# CW308T_ATMegaRF_Micro.net
KiCad netlist of a schematic drawn in Altium Designer
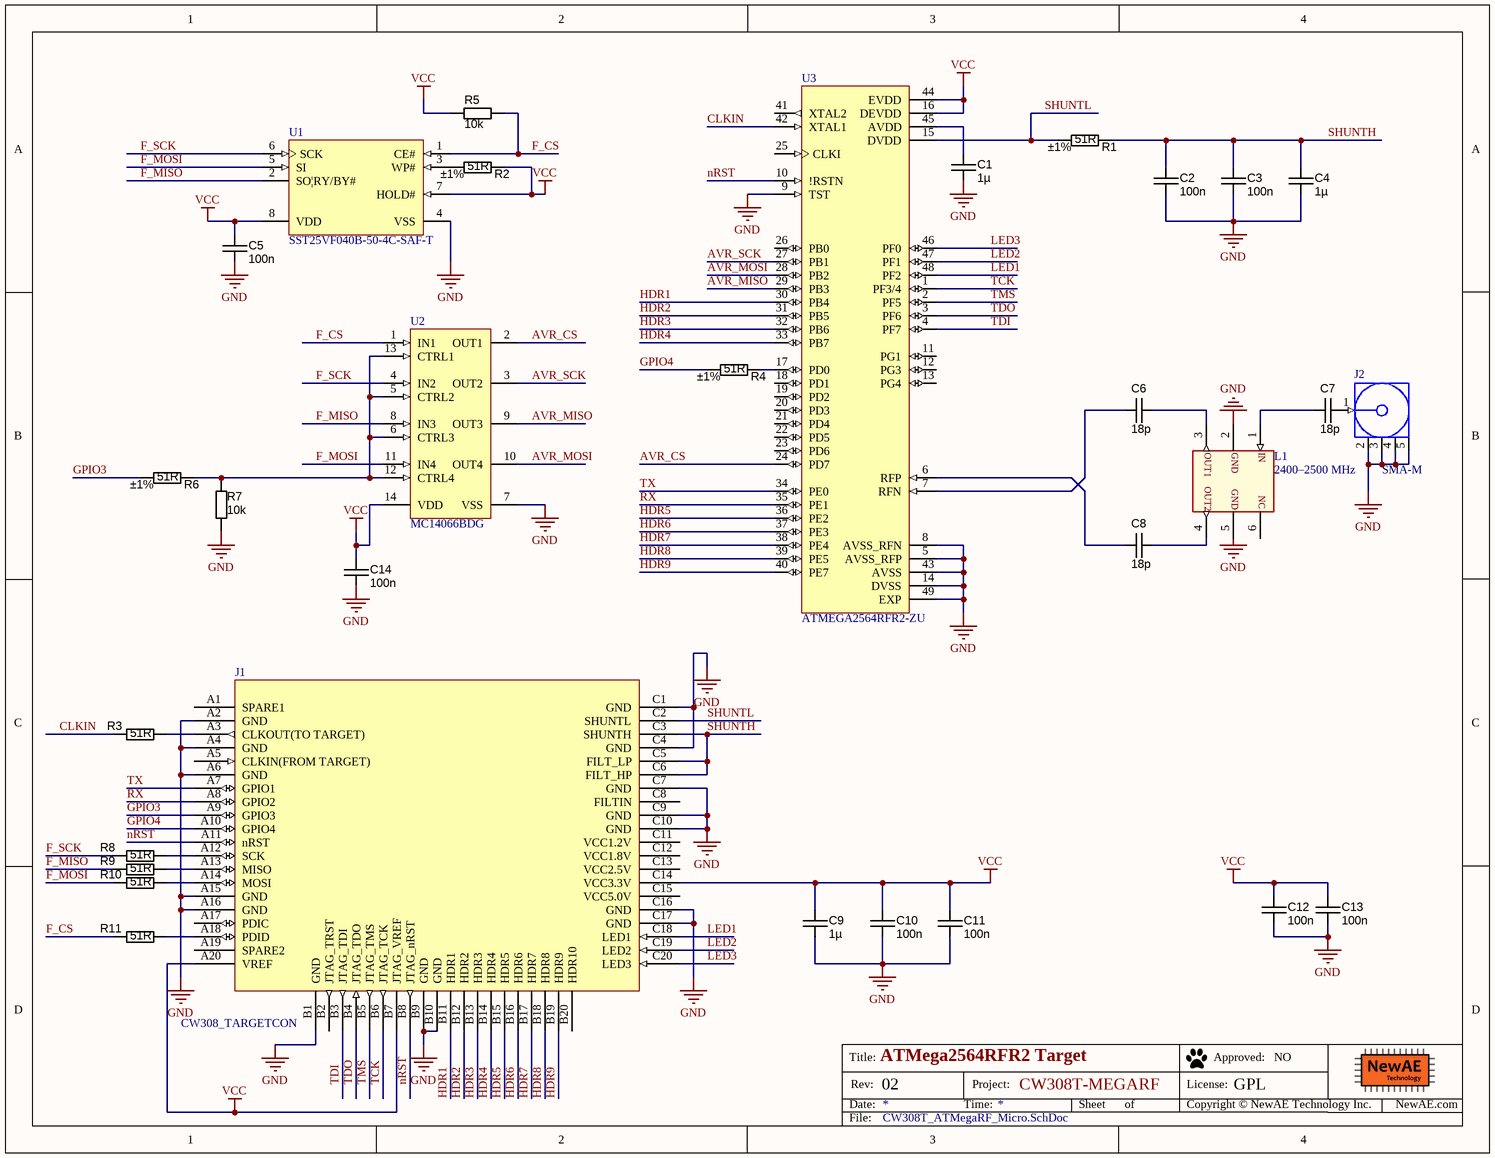
[diagram p0: CW308T_ATMegaRF_Micro.SchDoc]

(export (version "E")
  (design (tool "Eeschema 10.0.6"))
  (components
    (comp (ref "C1")
      (value "1µ")
      (footprint "CAPC1608X90N")
      (description "Capacitor SMD Cer 1uF 10% 16V X7R 0603")
      (fields (field (name "TOLERANCE") "±10%") (field (name "Comment") "approved sub OK"))
      (libsource (lib "PBL - Capacitors") (part "CAPC_1u_0603_X7R_16V_10%"))
    )
    (comp (ref "C2")
      (value "100n")
      (footprint "CAPC1608X90N")
      (description "Capacitor SMD Cer 100nF 10% 50V X7R 0603")
      (fields (field (name "TOLERANCE") "±10%") (field (name "Comment") "approved sub OK"))
      (libsource (lib "PBL - Capacitors") (part "CAPC_100n_0603_X7R_50V_10%"))
    )
    (comp (ref "C3")
      (value "100n")
      (footprint "CAPC1608X90N")
      (description "Capacitor SMD Cer 100nF 10% 50V X7R 0603")
      (fields (field (name "TOLERANCE") "±10%") (field (name "Comment") "approved sub OK"))
      (libsource (lib "PBL - Capacitors") (part "CAPC_100n_0603_X7R_50V_10%"))
    )
    (comp (ref "C4")
      (value "1µ")
      (footprint "CAPC1608X90N")
      (description "Capacitor SMD Cer 1uF 10% 16V X7R 0603")
      (fields (field (name "TOLERANCE") "±10%") (field (name "Comment") "approved sub OK"))
      (libsource (lib "PBL - Capacitors") (part "CAPC_1u_0603_X7R_16V_10%"))
    )
    (comp (ref "C5")
      (value "100n")
      (footprint "CAPC1608X90N")
      (description "Capacitor SMD Cer 100nF 10% 50V X7R 0603")
      (fields (field (name "TOLERANCE") "±10%") (field (name "Comment") "approved sub OK"))
      (libsource (lib "PBL - Capacitors") (part "CAPC_100n_0603_X7R_50V_10%"))
    )
    (comp (ref "C6")
      (value "18p")
      (footprint "CAPC1608X90N")
      (description "Capacitor SMD Cer 18pF 2% 100V NP0 0603")
      (fields (field (name "TOLERANCE") "±2%"))
      (libsource (lib "PBL - Capacitors") (part "CAPC_18p_0603_100V"))
    )
    (comp (ref "C7")
      (value "18p")
      (footprint "CAPC1608X90N")
      (description "Capacitor SMD Cer 18pF 2% 100V NP0 0603")
      (fields (field (name "TOLERANCE") "±2%"))
      (libsource (lib "PBL - Capacitors") (part "CAPC_18p_0603_100V"))
    )
    (comp (ref "C8")
      (value "18p")
      (footprint "CAPC1608X90N")
      (description "Capacitor SMD Cer 18pF 2% 100V NP0 0603")
      (fields (field (name "TOLERANCE") "±2%"))
      (libsource (lib "PBL - Capacitors") (part "CAPC_18p_0603_100V"))
    )
    (comp (ref "C9")
      (value "1µ")
      (footprint "CAPC1608X90N")
      (description "Capacitor SMD Cer 1uF 10% 16V X7R 0603")
      (fields (field (name "TOLERANCE") "±10%") (field (name "Comment") "approved sub OK"))
      (libsource (lib "PBL - Capacitors") (part "CAPC_1u_0603_X7R_16V_10%"))
    )
    (comp (ref "C10")
      (value "100n")
      (footprint "CAPC1608X90N")
      (description "Capacitor SMD Cer 100nF 10% 50V X7R 0603")
      (fields (field (name "TOLERANCE") "±10%") (field (name "Comment") "approved sub OK"))
      (libsource (lib "PBL - Capacitors") (part "CAPC_100n_0603_X7R_50V_10%"))
    )
    (comp (ref "C11")
      (value "100n")
      (footprint "CAPC1608X90N")
      (description "Capacitor SMD Cer 100nF 10% 50V X7R 0603")
      (fields (field (name "TOLERANCE") "±10%") (field (name "Comment") "approved sub OK"))
      (libsource (lib "PBL - Capacitors") (part "CAPC_100n_0603_X7R_50V_10%"))
    )
    (comp (ref "C12")
      (value "100n")
      (footprint "CAPC1608X90N")
      (description "Capacitor SMD Cer 100nF 10% 50V X7R 0603")
      (fields (field (name "TOLERANCE") "±10%") (field (name "Comment") "approved sub OK"))
      (libsource (lib "PBL - Capacitors") (part "CAPC_100n_0603_X7R_50V_10%"))
    )
    (comp (ref "C13")
      (value "100n")
      (footprint "CAPC1608X90N")
      (description "Capacitor SMD Cer 100nF 10% 50V X7R 0603")
      (fields (field (name "TOLERANCE") "±10%") (field (name "Comment") "approved sub OK"))
      (libsource (lib "PBL - Capacitors") (part "CAPC_100n_0603_X7R_50V_10%"))
    )
    (comp (ref "C14")
      (value "100n")
      (footprint "CAPC1608X90N")
      (description "Capacitor SMD Cer 100nF 10% 50V X7R 0603")
      (fields (field (name "TOLERANCE") "±10%") (field (name "Comment") "approved sub OK"))
      (libsource (lib "PBL - Capacitors") (part "CAPC_100n_0603_X7R_50V_10%"))
    )
    (comp (ref "J1")
      (value "CW308_TARGETCON")
      (footprint "ChipWhisperer_AltiumLib:CW308_TBOARD_CONN")
      (description "CW308 \"Standard\" Target Board Connector")
      (libsource (lib "ChipWhisperer_AltiumLib") (part "CW308_TBOARD"))
    )
    (comp (ref "J2")
      (value "SMA-M")
      (footprint "CON-SMAM-PCB-EDGE062")
      (description "SMA Female Edge Mount Connector for 0.062\" Thick Board")
      (libsource (lib "NewAE_AltiumLib") (part "CON-SMA-PCBEDGE-003.062"))
    )
    (comp (ref "L1")
      (value "2400–2500 MHz")
      (footprint "WE-BAL_0603")
      (description "WE-BAL Multilayer Chip Balun, Frequence=2400–2500 MHz")
      (fields
        (field (name "PARTNO") "748411245")
        (field (name "MANUFACTURER") "Wurth Elektronik")
        (field (name "CREATED BY") "Baojun Chen")
      )
      (libsource (lib "Altium_WE-BAL_rev15a") (part "WE-BAL 0603, 748411245"))
    )
    (comp (ref "R1")
      (value "51R")
      (footprint "RESC1608X55N")
      (description "Resistor SMD chip 51 Ohm 0.1W 1% 0603")
      (fields (field (name "TOLERANCE") "±1%") (field (name "Comment") "Thick Film"))
      (libsource (lib "PBL - Resistors") (part "RES_51R_0603_1%"))
    )
    (comp (ref "R2")
      (value "51R")
      (footprint "RESC1608X55N")
      (description "Resistor SMD chip 51 Ohm 0.1W 1% 0603")
      (fields (field (name "TOLERANCE") "±1%") (field (name "Comment") "Thick Film"))
      (libsource (lib "PBL - Resistors") (part "RES_51R_0603_1%"))
    )
    (comp (ref "R3")
      (value "51R")
      (footprint "RESC1608X55N")
      (description "Resistor SMD chip 51 Ohm 0.1W 1% 0603")
      (fields (field (name "Comment") "Thick Film"))
      (libsource (lib "PBL - Resistors") (part "RES_51R_0603_1%"))
    )
    (comp (ref "R4")
      (value "51R")
      (footprint "RESC1608X55N")
      (description "Resistor SMD chip 51 Ohm 0.1W 1% 0603")
      (fields (field (name "TOLERANCE") "±1%") (field (name "Comment") "Thick Film"))
      (libsource (lib "PBL - Resistors") (part "RES_51R_0603_1%"))
    )
    (comp (ref "R5")
      (value "10k")
      (footprint "RESC1608X55N")
      (description "Resistor SMD chip 3.3k Ohm 0.1W 5% 0603")
      (fields (field (name "TOLERANCE") "±5%") (field (name "Comment") "Thick Film"))
      (libsource (lib "PBL - Resistors") (part "RES_3K3_0603_5%"))
    )
    (comp (ref "R6")
      (value "51R")
      (footprint "RESC1608X55N")
      (description "Resistor SMD chip 51 Ohm 0.1W 1% 0603")
      (fields (field (name "TOLERANCE") "±1%") (field (name "Comment") "Thick Film"))
      (libsource (lib "PBL - Resistors") (part "RES_51R_0603_1%"))
    )
    (comp (ref "R7")
      (value "10k")
      (footprint "RESC1608X55N")
      (description "Resistor SMD chip 3.3k Ohm 0.1W 5% 0603")
      (fields (field (name "TOLERANCE") "±5%") (field (name "Comment") "Thick Film"))
      (libsource (lib "") (part "RES_3K3_0603_5%_1"))
    )
    (comp (ref "R8")
      (value "51R")
      (footprint "RESC1608X55N")
      (description "Resistor SMD chip 51 Ohm 0.1W 1% 0603")
      (fields (field (name "Comment") "Thick Film"))
      (libsource (lib "PBL - Resistors") (part "RES_51R_0603_1%"))
    )
    (comp (ref "R9")
      (value "51R")
      (footprint "RESC1608X55N")
      (description "Resistor SMD chip 51 Ohm 0.1W 1% 0603")
      (fields (field (name "Comment") "Thick Film"))
      (libsource (lib "PBL - Resistors") (part "RES_51R_0603_1%"))
    )
    (comp (ref "R10")
      (value "51R")
      (footprint "RESC1608X55N")
      (description "Resistor SMD chip 51 Ohm 0.1W 1% 0603")
      (fields (field (name "Comment") "Thick Film"))
      (libsource (lib "PBL - Resistors") (part "RES_51R_0603_1%"))
    )
    (comp (ref "R11")
      (value "51R")
      (footprint "RESC1608X55N")
      (description "Resistor SMD chip 51 Ohm 0.1W 1% 0603")
      (fields (field (name "Comment") "Thick Film"))
      (libsource (lib "PBL - Resistors") (part "RES_51R_0603_1%"))
    )
    (comp (ref "U1")
      (value "SST25VF040B-50-4C-SAF-T")
      (footprint "MCHP-SOIC-SA8_N")
      (description "4 Mbit SPI Serial Flash, 2.7 to 3.6 V, 50 MHz, 0 to 70 degC, 8-pin SOIC (SA8), Tape and Reel")
      (fields (field (name "MANUFACTURER") "Microchip"))
      (libsource (lib "Altium Content Vault") (part "CMP-0378-00095-1"))
    )
    (comp (ref "U2")
      (value "MC14066BDG")
      (footprint "ONSC-SOIC-14-751A-03_V")
      (description "Quad Analog Switch / Quad Multiplexer, 3 to 18 V, -55 to 125 degC, 14-Pin SOIC, Pb-Free, Tube")
      (fields (field (name "MANUFACTURER") "On Semiconductor"))
      (libsource (lib "Altium Content Vault") (part "CMP-1307-00073-1"))
    )
    (comp (ref "U3")
      (value "ATMEGA2564RFR2-ZU")
      (footprint "NewAE_AltiumLib:QFN50P700X700X100_HS-49M")
      (description "2.4GHZ 256k SOC 48pin Ind 125C MSL3 - 2.4GHZ 802.15.4 256K SOC 48pin Tray/ VQFN (ZB)")
      (libsource (lib "NewAE_AltiumLib") (part "ATMEGA2565RFR2-ZU"))
    )
  )
  (nets
    (net (code "1") (name "/AVR_CS") (class "Default")
      (node (ref "U2") (pin "2") (pinfunction "OUT1_2") (pintype "tri_state"))
      (node (ref "U3") (pin "24") (pinfunction "PD7_24") (pintype "bidirectional"))
    )
    (net (code "2") (name "/AVR_MISO") (class "Default")
      (node (ref "U2") (pin "9") (pinfunction "OUT3_9") (pintype "tri_state"))
      (node (ref "U3") (pin "29") (pinfunction "PB3_29") (pintype "bidirectional"))
    )
    (net (code "3") (name "/AVR_MOSI") (class "Default")
      (node (ref "U2") (pin "10") (pinfunction "OUT4_10") (pintype "tri_state"))
      (node (ref "U3") (pin "28") (pinfunction "PB2_28") (pintype "bidirectional"))
    )
    (net (code "4") (name "/AVR_SCK") (class "Default")
      (node (ref "U2") (pin "3") (pinfunction "OUT2_3") (pintype "tri_state"))
      (node (ref "U3") (pin "27") (pinfunction "PB1_27") (pintype "bidirectional"))
    )
    (net (code "5") (name "/CLKIN") (class "Default")
      (node (ref "R3") (pin "2") (pinfunction "2_2") (pintype "passive"))
      (node (ref "U3") (pin "42") (pinfunction "XTAL1_42") (pintype "input"))
    )
    (net (code "6") (name "/F_CS") (class "Default")
      (node (ref "R11") (pin "2") (pinfunction "2_2") (pintype "passive"))
      (node (ref "R5") (pin "2") (pinfunction "2_2") (pintype "passive"))
      (node (ref "U1") (pin "1") (pinfunction "CE#_1") (pintype "input"))
      (node (ref "U2") (pin "1") (pinfunction "IN1_1") (pintype "input"))
    )
    (net (code "7") (name "/F_MISO") (class "Default")
      (node (ref "R9") (pin "2") (pinfunction "2_2") (pintype "passive"))
      (node (ref "U1") (pin "2") (pinfunction "SO¦RY/BY#_2") (pintype "tri_state"))
      (node (ref "U2") (pin "8") (pinfunction "IN3_8") (pintype "input"))
    )
    (net (code "8") (name "/F_MOSI") (class "Default")
      (node (ref "R10") (pin "2") (pinfunction "2_2") (pintype "passive"))
      (node (ref "U1") (pin "5") (pinfunction "SI_5") (pintype "input"))
      (node (ref "U2") (pin "11") (pinfunction "IN4_11") (pintype "input"))
    )
    (net (code "9") (name "/F_SCK") (class "Default")
      (node (ref "R8") (pin "2") (pinfunction "2_2") (pintype "passive"))
      (node (ref "U1") (pin "6") (pinfunction "SCK_6") (pintype "input"))
      (node (ref "U2") (pin "4") (pinfunction "IN2_4") (pintype "input"))
    )
    (net (code "10") (name "/GPIO3") (class "Default")
      (node (ref "J1") (pin "A9") (pinfunction "GPIO3_A9") (pintype "bidirectional"))
      (node (ref "R6") (pin "2") (pinfunction "2_2") (pintype "passive"))
    )
    (net (code "11") (name "/GPIO4") (class "Default")
      (node (ref "J1") (pin "A10") (pinfunction "GPIO4_A10") (pintype "bidirectional"))
      (node (ref "R4") (pin "2") (pinfunction "2_2") (pintype "passive"))
    )
    (net (code "12") (name "/HDR1") (class "Default")
      (node (ref "J1") (pin "B11") (pinfunction "HDR1_B11") (pintype "passive"))
      (node (ref "U3") (pin "30") (pinfunction "PB4_30") (pintype "bidirectional"))
    )
    (net (code "13") (name "/HDR2") (class "Default")
      (node (ref "J1") (pin "B12") (pinfunction "HDR2_B12") (pintype "passive"))
      (node (ref "U3") (pin "31") (pinfunction "PB5_31") (pintype "bidirectional"))
    )
    (net (code "14") (name "/HDR3") (class "Default")
      (node (ref "J1") (pin "B13") (pinfunction "HDR3_B13") (pintype "passive"))
      (node (ref "U3") (pin "32") (pinfunction "PB6_32") (pintype "bidirectional"))
    )
    (net (code "15") (name "/HDR4") (class "Default")
      (node (ref "J1") (pin "B14") (pinfunction "HDR4_B14") (pintype "passive"))
      (node (ref "U3") (pin "33") (pinfunction "PB7_33") (pintype "bidirectional"))
    )
    (net (code "16") (name "/HDR5") (class "Default")
      (node (ref "J1") (pin "B15") (pinfunction "HDR5_B15") (pintype "passive"))
      (node (ref "U3") (pin "36") (pinfunction "PE2_36") (pintype "bidirectional"))
    )
    (net (code "17") (name "/HDR6") (class "Default")
      (node (ref "J1") (pin "B16") (pinfunction "HDR6_B16") (pintype "passive"))
      (node (ref "U3") (pin "37") (pinfunction "PE3_37") (pintype "bidirectional"))
    )
    (net (code "18") (name "/HDR7") (class "Default")
      (node (ref "J1") (pin "B17") (pinfunction "HDR7_B17") (pintype "passive"))
      (node (ref "U3") (pin "38") (pinfunction "PE4_38") (pintype "bidirectional"))
    )
    (net (code "19") (name "/HDR8") (class "Default")
      (node (ref "J1") (pin "B18") (pinfunction "HDR8_B18") (pintype "passive"))
      (node (ref "U3") (pin "39") (pinfunction "PE5_39") (pintype "bidirectional"))
    )
    (net (code "20") (name "/HDR9") (class "Default")
      (node (ref "J1") (pin "B19") (pinfunction "HDR9_B19") (pintype "passive"))
      (node (ref "U3") (pin "40") (pinfunction "PE7_40") (pintype "bidirectional"))
    )
    (net (code "21") (name "/LED1") (class "Default")
      (node (ref "J1") (pin "C18") (pinfunction "LED1_C18") (pintype "input"))
      (node (ref "U3") (pin "48") (pinfunction "PF2_48") (pintype "bidirectional"))
    )
    (net (code "22") (name "/LED2") (class "Default")
      (node (ref "J1") (pin "C19") (pinfunction "LED2_C19") (pintype "input"))
      (node (ref "U3") (pin "47") (pinfunction "PF1_47") (pintype "bidirectional"))
    )
    (net (code "23") (name "/LED3") (class "Default")
      (node (ref "J1") (pin "C20") (pinfunction "LED3_C20") (pintype "input"))
      (node (ref "U3") (pin "46") (pinfunction "PF0_46") (pintype "bidirectional"))
    )
    (net (code "24") (name "/RX") (class "Default")
      (node (ref "J1") (pin "A8") (pinfunction "GPIO2_A8") (pintype "bidirectional"))
      (node (ref "U3") (pin "35") (pinfunction "PE1_35") (pintype "bidirectional"))
    )
    (net (code "25") (name "/SHUNTH") (class "Default")
      (node (ref "C2") (pin "1") (pintype "passive"))
      (node (ref "C3") (pin "1") (pintype "passive"))
      (node (ref "C4") (pin "1") (pintype "passive"))
      (node (ref "J1") (pin "C3") (pinfunction "SHUNTH_C3") (pintype "passive"))
      (node (ref "J1") (pin "C5") (pinfunction "FILT_LP_C5") (pintype "passive"))
      (node (ref "J1") (pin "C6") (pinfunction "FILT_HP_C6") (pintype "passive"))
      (node (ref "R1") (pin "1") (pinfunction "1_1") (pintype "passive"))
    )
    (net (code "26") (name "/SHUNTL") (class "Default")
      (node (ref "J1") (pin "C2") (pinfunction "SHUNTL_C2") (pintype "passive"))
      (node (ref "R1") (pin "2") (pinfunction "2_2") (pintype "passive"))
      (node (ref "U3") (pin "15") (pinfunction "DVDD_15") (pintype "power_in"))
    )
    (net (code "27") (name "/TCK") (class "Default")
      (node (ref "J1") (pin "B6") (pinfunction "JTAG_TCK_B6") (pintype "output"))
      (node (ref "U3") (pin "1") (pinfunction "PF3/4_1") (pintype "bidirectional"))
    )
    (net (code "28") (name "/TDI") (class "Default")
      (node (ref "J1") (pin "B3") (pinfunction "JTAG_TDI_B3") (pintype "output"))
      (node (ref "U3") (pin "4") (pinfunction "PF7_4") (pintype "bidirectional"))
    )
    (net (code "29") (name "/TDO") (class "Default")
      (node (ref "J1") (pin "B4") (pinfunction "JTAG_TDO_B4") (pintype "input"))
      (node (ref "U3") (pin "3") (pinfunction "PF6_3") (pintype "bidirectional"))
    )
    (net (code "30") (name "/TMS") (class "Default")
      (node (ref "J1") (pin "B5") (pinfunction "JTAG_TMS_B5") (pintype "output"))
      (node (ref "U3") (pin "2") (pinfunction "PF5_2") (pintype "bidirectional"))
    )
    (net (code "31") (name "/TX") (class "Default")
      (node (ref "J1") (pin "A7") (pinfunction "GPIO1_A7") (pintype "bidirectional"))
      (node (ref "U3") (pin "34") (pinfunction "PE0_34") (pintype "bidirectional"))
    )
    (net (code "32") (name "/nRST") (class "Default")
      (node (ref "J1") (pin "A11") (pinfunction "nRST_A11") (pintype "bidirectional"))
      (node (ref "J1") (pin "B8") (pinfunction "JTAG_nRST_B8") (pintype "output"))
      (node (ref "U3") (pin "10") (pinfunction "!RSTN_10") (pintype "input"))
    )
    (net (code "33") (name "GND") (class "Default")
      (node (ref "C1") (pin "2") (pintype "passive"))
      (node (ref "C10") (pin "2") (pintype "passive"))
      (node (ref "C11") (pin "2") (pintype "passive"))
      (node (ref "C12") (pin "2") (pintype "passive"))
      (node (ref "C13") (pin "2") (pintype "passive"))
      (node (ref "C14") (pin "2") (pintype "passive"))
      (node (ref "C2") (pin "2") (pintype "passive"))
      (node (ref "C3") (pin "2") (pintype "passive"))
      (node (ref "C4") (pin "2") (pintype "passive"))
      (node (ref "C5") (pin "2") (pintype "passive"))
      (node (ref "C9") (pin "2") (pintype "passive"))
      (node (ref "J1") (pin "A15") (pinfunction "GND_A15") (pintype "passive"))
      (node (ref "J1") (pin "A16") (pinfunction "GND_A16") (pintype "passive"))
      (node (ref "J1") (pin "A2") (pinfunction "GND_A2") (pintype "passive"))
      (node (ref "J1") (pin "A4") (pinfunction "GND_A4") (pintype "passive"))
      (node (ref "J1") (pin "A6") (pinfunction "GND_A6") (pintype "power_in"))
      (node (ref "J1") (pin "B1") (pinfunction "GND_B1") (pintype "passive"))
      (node (ref "J1") (pin "B10") (pinfunction "GND_B10") (pintype "passive"))
      (node (ref "J1") (pin "B9") (pinfunction "GND_B9") (pintype "passive"))
      (node (ref "J1") (pin "C1") (pinfunction "GND_C1") (pintype "power_in"))
      (node (ref "J1") (pin "C10") (pinfunction "GND_C10") (pintype "power_in"))
      (node (ref "J1") (pin "C16") (pinfunction "GND_C16") (pintype "power_in"))
      (node (ref "J1") (pin "C17") (pinfunction "GND_C17") (pintype "power_in"))
      (node (ref "J1") (pin "C4") (pinfunction "GND_C4") (pintype "power_in"))
      (node (ref "J1") (pin "C7") (pinfunction "GND_C7") (pintype "power_in"))
      (node (ref "J1") (pin "C9") (pinfunction "GND_C9") (pintype "power_in"))
      (node (ref "J2") (pin "2") (pinfunction "GND_2") (pintype "power_in"))
      (node (ref "J2") (pin "3") (pinfunction "GND_3") (pintype "power_in"))
      (node (ref "J2") (pin "4") (pinfunction "GND_4") (pintype "power_in"))
      (node (ref "J2") (pin "5") (pinfunction "GND_5") (pintype "power_in"))
      (node (ref "L1") (pin "2") (pinfunction "GND_2") (pintype "passive"))
      (node (ref "R7") (pin "1") (pinfunction "1_1") (pintype "passive"))
      (node (ref "U1") (pin "4") (pinfunction "VSS_4") (pintype "power_in"))
      (node (ref "U2") (pin "7") (pinfunction "VSS_7") (pintype "power_in"))
      (node (ref "U3") (pin "14") (pinfunction "DVSS_14") (pintype "power_in"))
      (node (ref "U3") (pin "43") (pinfunction "AVSS_43") (pintype "power_in"))
      (node (ref "U3") (pin "49") (pinfunction "EXP_49") (pintype "passive"))
      (node (ref "U3") (pin "5") (pinfunction "AVSS_RFP_5") (pintype "power_in"))
      (node (ref "U3") (pin "8") (pinfunction "AVSS_RFN_8") (pintype "power_in"))
      (node (ref "U3") (pin "9") (pinfunction "TST_9") (pintype "input"))
    )
    (net (code "34") (name "Net-(J1-CLKOUT(TO_TARGET))") (class "Default")
      (node (ref "J1") (pin "A3") (pinfunction "CLKOUT(TO_TARGET)_A3") (pintype "output"))
      (node (ref "R3") (pin "1") (pinfunction "1_1") (pintype "passive"))
    )
    (net (code "35") (name "Net-(J1-MISO)") (class "Default")
      (node (ref "J1") (pin "A13") (pinfunction "MISO_A13") (pintype "bidirectional"))
      (node (ref "R9") (pin "1") (pinfunction "1_1") (pintype "passive"))
    )
    (net (code "36") (name "Net-(J1-MOSI)") (class "Default")
      (node (ref "J1") (pin "A14") (pinfunction "MOSI_A14") (pintype "bidirectional"))
      (node (ref "R10") (pin "1") (pinfunction "1_1") (pintype "passive"))
    )
    (net (code "37") (name "Net-(J1-PDID)") (class "Default")
      (node (ref "J1") (pin "A18") (pinfunction "PDID_A18") (pintype "bidirectional"))
      (node (ref "R11") (pin "1") (pinfunction "1_1") (pintype "passive"))
    )
    (net (code "38") (name "Net-(J1-SCK)") (class "Default")
      (node (ref "J1") (pin "A12") (pinfunction "SCK_A12") (pintype "bidirectional"))
      (node (ref "R8") (pin "1") (pinfunction "1_1") (pintype "passive"))
    )
    (net (code "39") (name "Net-(J2-Signal)") (class "Default")
      (node (ref "C7") (pin "2") (pintype "passive"))
      (node (ref "J2") (pin "1") (pinfunction "Signal_1") (pintype "input"))
    )
    (net (code "40") (name "Net-(L1-IN)") (class "Default")
      (node (ref "C7") (pin "1") (pintype "passive"))
      (node (ref "L1") (pin "1") (pinfunction "IN_1") (pintype "input"))
    )
    (net (code "41") (name "Net-(L1-OUT1)") (class "Default")
      (node (ref "C6") (pin "2") (pintype "passive"))
      (node (ref "L1") (pin "3") (pinfunction "OUT1_3") (pintype "output"))
    )
    (net (code "42") (name "Net-(L1-OUT2)") (class "Default")
      (node (ref "C8") (pin "2") (pintype "passive"))
      (node (ref "L1") (pin "4") (pinfunction "OUT2_4") (pintype "output"))
    )
    (net (code "43") (name "Net-(U1-WP#)") (class "Default")
      (node (ref "R2") (pin "2") (pinfunction "2_2") (pintype "passive"))
      (node (ref "U1") (pin "3") (pinfunction "WP#_3") (pintype "input"))
    )
    (net (code "44") (name "Net-(U2-CTRL1)") (class "Default")
      (node (ref "R6") (pin "1") (pinfunction "1_1") (pintype "passive"))
      (node (ref "R7") (pin "2") (pinfunction "2_2") (pintype "passive"))
      (node (ref "U2") (pin "12") (pinfunction "CTRL4_12") (pintype "input"))
      (node (ref "U2") (pin "13") (pinfunction "CTRL1_13") (pintype "input"))
      (node (ref "U2") (pin "5") (pinfunction "CTRL2_5") (pintype "input"))
      (node (ref "U2") (pin "6") (pinfunction "CTRL3_6") (pintype "input"))
    )
    (net (code "45") (name "Net-(U3-AVDD)") (class "Default")
      (node (ref "C1") (pin "1") (pintype "passive"))
      (node (ref "U3") (pin "45") (pinfunction "AVDD_45") (pintype "power_in"))
    )
    (net (code "46") (name "Net-(U3-PD0)") (class "Default")
      (node (ref "R4") (pin "1") (pinfunction "1_1") (pintype "passive"))
      (node (ref "U3") (pin "17") (pinfunction "PD0_17") (pintype "bidirectional"))
    )
    (net (code "47") (name "Net-(U3-RFN)") (class "Default")
      (node (ref "C6") (pin "1") (pintype "passive"))
      (node (ref "U3") (pin "7") (pinfunction "RFN_7") (pintype "input"))
    )
    (net (code "48") (name "Net-(U3-RFP)") (class "Default")
      (node (ref "C8") (pin "1") (pintype "passive"))
      (node (ref "U3") (pin "6") (pinfunction "RFP_6") (pintype "input"))
    )
    (net (code "49") (name "VCC") (class "Default")
      (node (ref "C10") (pin "1") (pintype "passive"))
      (node (ref "C11") (pin "1") (pintype "passive"))
      (node (ref "C12") (pin "1") (pintype "passive"))
      (node (ref "C13") (pin "1") (pintype "passive"))
      (node (ref "C14") (pin "1") (pintype "passive"))
      (node (ref "C5") (pin "1") (pintype "passive"))
      (node (ref "C9") (pin "1") (pintype "passive"))
      (node (ref "J1") (pin "A20") (pinfunction "VREF_A20") (pintype "tri_state"))
      (node (ref "J1") (pin "B7") (pinfunction "JTAG_VREF_B7") (pintype "tri_state"))
      (node (ref "J1") (pin "C14") (pinfunction "VCC3.3V_C14") (pintype "power_in"))
      (node (ref "R2") (pin "1") (pinfunction "1_1") (pintype "passive"))
      (node (ref "R5") (pin "1") (pinfunction "1_1") (pintype "passive"))
      (node (ref "U1") (pin "7") (pinfunction "HOLD#_7") (pintype "input"))
      (node (ref "U1") (pin "8") (pinfunction "VDD_8") (pintype "power_in"))
      (node (ref "U2") (pin "14") (pinfunction "VDD_14") (pintype "power_in"))
      (node (ref "U3") (pin "16") (pinfunction "DEVDD_16") (pintype "power_in"))
      (node (ref "U3") (pin "44") (pinfunction "EVDD_44") (pintype "power_in"))
    )
    (net (code "50") (name "unconnected-(J1-CLKIN(FROM_TARGET)-PadA5)") (class "Default")
      (node (ref "J1") (pin "A5") (pinfunction "CLKIN(FROM_TARGET)_A5") (pintype "input"))
    )
    (net (code "51") (name "unconnected-(J1-FILTIN-PadC8)") (class "Default")
      (node (ref "J1") (pin "C8") (pinfunction "FILTIN_C8") (pintype "passive"))
    )
    (net (code "52") (name "unconnected-(J1-HDR10-PadB20)") (class "Default")
      (node (ref "J1") (pin "B20") (pinfunction "HDR10_B20") (pintype "passive"))
    )
    (net (code "53") (name "unconnected-(J1-JTAG_TRST-PadB2)") (class "Default")
      (node (ref "J1") (pin "B2") (pinfunction "JTAG_TRST_B2") (pintype "output"))
    )
    (net (code "54") (name "unconnected-(J1-PDIC-PadA17)") (class "Default")
      (node (ref "J1") (pin "A17") (pinfunction "PDIC_A17") (pintype "bidirectional"))
    )
    (net (code "55") (name "unconnected-(J1-SPARE1-PadA1)") (class "Default")
      (node (ref "J1") (pin "A1") (pinfunction "SPARE1_A1") (pintype "passive"))
    )
    (net (code "56") (name "unconnected-(J1-SPARE2-PadA19)") (class "Default")
      (node (ref "J1") (pin "A19") (pinfunction "SPARE2_A19") (pintype "passive"))
    )
    (net (code "57") (name "unconnected-(J1-VCC1.2V-PadC11)") (class "Default")
      (node (ref "J1") (pin "C11") (pinfunction "VCC1.2V_C11") (pintype "power_in"))
    )
    (net (code "58") (name "unconnected-(J1-VCC1.8V-PadC12)") (class "Default")
      (node (ref "J1") (pin "C12") (pinfunction "VCC1.8V_C12") (pintype "power_in"))
    )
    (net (code "59") (name "unconnected-(J1-VCC2.5V-PadC13)") (class "Default")
      (node (ref "J1") (pin "C13") (pinfunction "VCC2.5V_C13") (pintype "power_in"))
    )
    (net (code "60") (name "unconnected-(J1-VCC5.0V-PadC15)") (class "Default")
      (node (ref "J1") (pin "C15") (pinfunction "VCC5.0V_C15") (pintype "power_in"))
    )
    (net (code "61") (name "unconnected-(L1-GND-Pad5)") (class "Default")
      (node (ref "L1") (pin "5") (pinfunction "GND_5") (pintype "passive"))
    )
    (net (code "62") (name "unconnected-(L1-NC-Pad6)") (class "Default")
      (node (ref "L1") (pin "6") (pinfunction "NC_6") (pintype "passive"))
    )
    (net (code "63") (name "unconnected-(U3-CLKI-Pad25)") (class "Default")
      (node (ref "U3") (pin "25") (pinfunction "CLKI_25") (pintype "input"))
    )
    (net (code "64") (name "unconnected-(U3-PB0-Pad26)") (class "Default")
      (node (ref "U3") (pin "26") (pinfunction "PB0_26") (pintype "bidirectional"))
    )
    (net (code "65") (name "unconnected-(U3-PD1-Pad18)") (class "Default")
      (node (ref "U3") (pin "18") (pinfunction "PD1_18") (pintype "bidirectional"))
    )
    (net (code "66") (name "unconnected-(U3-PD2-Pad19)") (class "Default")
      (node (ref "U3") (pin "19") (pinfunction "PD2_19") (pintype "bidirectional"))
    )
    (net (code "67") (name "unconnected-(U3-PD3-Pad20)") (class "Default")
      (node (ref "U3") (pin "20") (pinfunction "PD3_20") (pintype "bidirectional"))
    )
    (net (code "68") (name "unconnected-(U3-PD4-Pad21)") (class "Default")
      (node (ref "U3") (pin "21") (pinfunction "PD4_21") (pintype "bidirectional"))
    )
    (net (code "69") (name "unconnected-(U3-PD5-Pad22)") (class "Default")
      (node (ref "U3") (pin "22") (pinfunction "PD5_22") (pintype "bidirectional"))
    )
    (net (code "70") (name "unconnected-(U3-PD6-Pad23)") (class "Default")
      (node (ref "U3") (pin "23") (pinfunction "PD6_23") (pintype "bidirectional"))
    )
    (net (code "71") (name "unconnected-(U3-PG1-Pad11)") (class "Default")
      (node (ref "U3") (pin "11") (pinfunction "PG1_11") (pintype "bidirectional"))
    )
    (net (code "72") (name "unconnected-(U3-PG3-Pad12)") (class "Default")
      (node (ref "U3") (pin "12") (pinfunction "PG3_12") (pintype "bidirectional"))
    )
    (net (code "73") (name "unconnected-(U3-PG4-Pad13)") (class "Default")
      (node (ref "U3") (pin "13") (pinfunction "PG4_13") (pintype "bidirectional"))
    )
    (net (code "74") (name "unconnected-(U3-XTAL2-Pad41)") (class "Default")
      (node (ref "U3") (pin "41") (pinfunction "XTAL2_41") (pintype "output"))
    )
  )
)
